# Regulators.net
KiCad netlist of a schematic drawn in Altium Designer
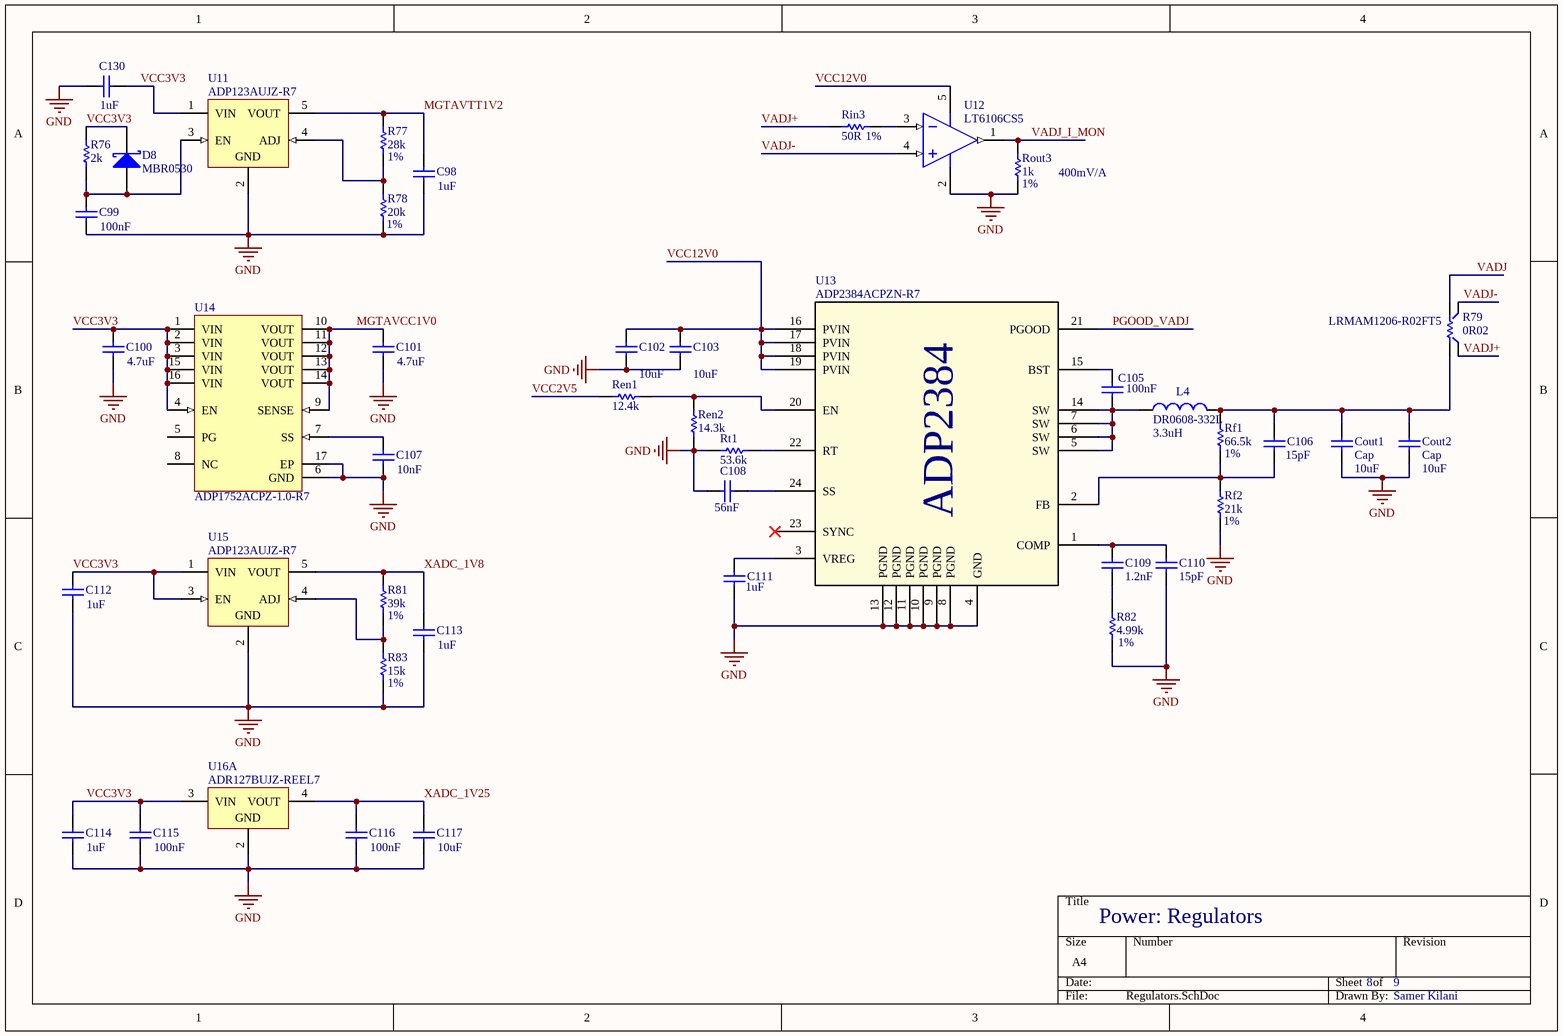
[diagram p0: Regulators.SchDoc]

(export (version "E")
  (design (tool "Eeschema 10.0.6"))
  (components
    (comp (ref "C98")
      (value "1uF")
      (footprint "C0603")
      (description "Capacitor")
      (fields (field (name "PUBLISHER") "Altium Limited"))
      (libsource (lib "atfclib") (part "Cap"))
    )
    (comp (ref "C99")
      (value "100nF")
      (footprint "C0402")
      (description "Capacitor")
      (fields (field (name "PUBLISHER") "Altium Limited"))
      (libsource (lib "atfclib") (part "Cap"))
    )
    (comp (ref "C100")
      (value "4.7uF")
      (footprint "C0603")
      (description "Capacitor")
      (fields (field (name "PUBLISHER") "Altium Limited"))
      (libsource (lib "atfclib") (part "Cap"))
    )
    (comp (ref "C101")
      (value "4.7uF")
      (footprint "C0603")
      (description "Capacitor")
      (fields (field (name "PUBLISHER") "Altium Limited"))
      (libsource (lib "atfclib") (part "Cap"))
    )
    (comp (ref "C102")
      (value "10uF")
      (footprint "C0805")
      (description "Capacitor")
      (fields (field (name "PUBLISHER") "Altium Limited"))
      (libsource (lib "atfclib") (part "Cap"))
    )
    (comp (ref "C103")
      (value "10uF")
      (footprint "C0805")
      (description "Capacitor")
      (fields (field (name "PUBLISHER") "Altium Limited"))
      (libsource (lib "atfclib") (part "Cap"))
    )
    (comp (ref "C105")
      (value "100nF")
      (footprint "C0402")
      (description "Capacitor")
      (fields (field (name "Comment") "Cap") (field (name "PUBLISHER") "Altium Limited"))
      (libsource (lib "atfclib") (part "Cap"))
    )
    (comp (ref "C106")
      (value "15pF")
      (footprint "C0402")
      (description "Capacitor")
      (fields (field (name "PUBLISHER") "Altium Limited"))
      (libsource (lib "atfclib") (part "Cap"))
    )
    (comp (ref "C107")
      (value "10nF")
      (footprint "C0603")
      (description "Capacitor")
      (fields (field (name "PUBLISHER") "Altium Limited"))
      (libsource (lib "atfclib") (part "Cap"))
    )
    (comp (ref "C108")
      (value "56nF")
      (footprint "C0402")
      (description "Capacitor")
      (fields (field (name "PUBLISHER") "Altium Limited"))
      (libsource (lib "atfclib") (part "Cap"))
    )
    (comp (ref "C109")
      (value "1.2nF")
      (footprint "C0402")
      (description "Capacitor")
      (fields (field (name "PUBLISHER") "Altium Limited"))
      (libsource (lib "atfclib") (part "Cap"))
    )
    (comp (ref "C110")
      (value "15pF")
      (footprint "C0402")
      (description "Capacitor")
      (fields (field (name "PUBLISHER") "Altium Limited"))
      (libsource (lib "atfclib") (part "Cap"))
    )
    (comp (ref "C111")
      (value "1uF")
      (footprint "C0402")
      (description "Capacitor")
      (fields (field (name "PUBLISHER") "Altium Limited"))
      (libsource (lib "atfclib") (part "Cap"))
    )
    (comp (ref "C112")
      (value "1uF")
      (footprint "C0603")
      (description "Capacitor")
      (fields (field (name "PUBLISHER") "Altium Limited"))
      (libsource (lib "atfclib") (part "Cap"))
    )
    (comp (ref "C113")
      (value "1uF")
      (footprint "C0603")
      (description "Capacitor")
      (fields (field (name "PUBLISHER") "Altium Limited"))
      (libsource (lib "atfclib") (part "Cap"))
    )
    (comp (ref "C114")
      (value "1uF")
      (footprint "C0603")
      (description "Capacitor")
      (fields (field (name "PUBLISHER") "Altium Limited"))
      (libsource (lib "atfclib") (part "Cap"))
    )
    (comp (ref "C115")
      (value "100nF")
      (footprint "C0402")
      (description "Capacitor")
      (fields (field (name "PUBLISHER") "Altium Limited"))
      (libsource (lib "atfclib") (part "Cap"))
    )
    (comp (ref "C116")
      (value "100nF")
      (footprint "C0402")
      (description "Capacitor")
      (fields (field (name "PUBLISHER") "Altium Limited"))
      (libsource (lib "atfclib") (part "Cap"))
    )
    (comp (ref "C117")
      (value "10uF")
      (footprint "C0603")
      (description "Capacitor")
      (fields (field (name "PUBLISHER") "Altium Limited"))
      (libsource (lib "atfclib") (part "Cap"))
    )
    (comp (ref "C130")
      (value "1uF")
      (footprint "C0603")
      (description "Capacitor")
      (fields (field (name "PUBLISHER") "Altium Limited"))
      (libsource (lib "atfclib") (part "Cap"))
    )
    (comp (ref "Cout1")
      (value "Cap")
      (footprint "C0805")
      (description "Capacitor")
      (fields (field (name "ALTIUM_VALUE") "10uF") (field (name "PUBLISHER") "Altium Limited"))
      (libsource (lib "atfclib") (part "Cap"))
    )
    (comp (ref "Cout2")
      (value "Cap")
      (footprint "C0805")
      (description "Capacitor")
      (fields (field (name "ALTIUM_VALUE") "10uF") (field (name "PUBLISHER") "Altium Limited"))
      (libsource (lib "atfclib") (part "Cap"))
    )
    (comp (ref "D8") (value "MBR0530") (footprint "SOD-123") (libsource (lib "atfclib") (part "MBR0530")))
    (comp (ref "L4")
      (value "DR0608-332L")
      (footprint "DR0608")
      (description "Inductor")
      (fields (field (name "ALTIUM_VALUE") "3.3uH") (field (name "PUBLISHER") "Altium Limited"))
      (libsource (lib "atfclib") (part "Inductor"))
    )
    (comp (ref "R76")
      (value "2k")
      (footprint "R0402")
      (description "Resistor")
      (fields (field (name "Comment") "Res"))
      (libsource (lib "atfclib") (part "Res"))
    )
    (comp (ref "R77")
      (value "28k")
      (footprint "R0402")
      (description "Resistor")
      (fields (field (name "TOLERANCE") "1%") (field (name "Comment") "Res"))
      (libsource (lib "atfclib") (part "Res"))
    )
    (comp (ref "R78")
      (value "20k")
      (footprint "R0402")
      (description "Resistor")
      (fields (field (name "TOLERANCE") "1%") (field (name "Comment") "Res"))
      (libsource (lib "atfclib") (part "Res"))
    )
    (comp (ref "R79")
      (value "LRMAM1206-R02FT5")
      (footprint "LRMA1206")
      (description "Resistor")
      (fields (field (name "ALTIUM_VALUE") "0R02"))
      (libsource (lib "atfclib") (part "Res_sense"))
    )
    (comp (ref "R81")
      (value "39k")
      (footprint "R0603")
      (description "Resistor")
      (fields (field (name "TOLERANCE") "1%") (field (name "Comment") "Res"))
      (libsource (lib "atfclib") (part "Res"))
    )
    (comp (ref "R82")
      (value "4.99k")
      (footprint "R0402")
      (description "Resistor")
      (fields (field (name "TOLERANCE") "1%") (field (name "Comment") "Res"))
      (libsource (lib "atfclib") (part "Res"))
    )
    (comp (ref "R83")
      (value "15k")
      (footprint "R0603")
      (description "Resistor")
      (fields (field (name "TOLERANCE") "1%") (field (name "Comment") "Res"))
      (libsource (lib "atfclib") (part "Res"))
    )
    (comp (ref "Ren1")
      (value "12.4k")
      (footprint "R0402")
      (description "Resistor")
      (fields (field (name "Comment") "Res"))
      (libsource (lib "atfclib") (part "Res"))
    )
    (comp (ref "Ren2")
      (value "14.3k")
      (footprint "R0402")
      (description "Resistor")
      (fields (field (name "Comment") "Res"))
      (libsource (lib "atfclib") (part "Res"))
    )
    (comp (ref "Rf1")
      (value "66.5k")
      (footprint "R0402")
      (description "Resistor")
      (fields (field (name "TOLERANCE") "1%") (field (name "Comment") "Res"))
      (libsource (lib "atfclib") (part "Res"))
    )
    (comp (ref "Rf2")
      (value "21k")
      (footprint "R0402")
      (description "Resistor")
      (fields (field (name "TOLERANCE") "1%") (field (name "Comment") "Res"))
      (libsource (lib "atfclib") (part "Res"))
    )
    (comp (ref "Rin3")
      (value "50R")
      (footprint "R0402")
      (description "Resistor")
      (fields (field (name "TOLERANCE") "1%") (field (name "Comment") "Res"))
      (libsource (lib "atfclib") (part "Res"))
    )
    (comp (ref "Rout3")
      (value "1k")
      (footprint "R0402")
      (description "Resistor")
      (fields (field (name "TOLERANCE") "1%") (field (name "Comment") "Res"))
      (libsource (lib "atfclib") (part "Res"))
    )
    (comp (ref "Rt1")
      (value "53.6k")
      (footprint "R0402")
      (description "Resistor")
      (fields (field (name "Comment") "Res"))
      (libsource (lib "atfclib") (part "Res"))
    )
    (comp (ref "U11")
      (value "ADP123AUJZ-R7")
      (footprint "ADI-UJ-5_N")
      (fields (field (name "MANUFACTURER") "Analog Devices"))
      (libsource (lib "atfclib") (part "ADP123AUJZ-R7"))
    )
    (comp (ref "U12")
      (value "LT6106CS5")
      (footprint "LT-S5-5-TSOT-23_N")
      (fields
        (field (name "LINEAR TECHNOLOGY PART NUMBER") "LT6106")
        (field (name "MANUFACTURER") "Linear Technology")
      )
      (libsource (lib "atfclib") (part "LT6106CS5"))
    )
    (comp (ref "U13")
      (value "ADP2384ACPZN-R7")
      (footprint "CP_24_12")
      (description "Imported")
      (libsource (lib "atfclib") (part "ADP2384ACPZN-R7"))
    )
    (comp (ref "U14")
      (value "ADP1752ACPZ-1.0-R7")
      (footprint "CP-16-4_N")
      (fields (field (name "MANUFACTURER") "Analog Devices"))
      (libsource (lib "atfclib") (part "ADP1752ACPZ-1.0-R7"))
    )
    (comp (ref "U15")
      (value "ADP123AUJZ-R7")
      (footprint "ADI-UJ-5_N")
      (fields (field (name "MANUFACTURER") "Analog Devices"))
      (libsource (lib "atfclib") (part "ADP123AUJZ-R7"))
    )
    (comp (ref "U16")
      (value "ADR127BUJZ-REEL7")
      (footprint "ADI-UJ-6_N")
      (fields (field (name "MANUFACTURER") "Analog Devices"))
      (libsource (lib "atfclib") (part "ADR127BUJZ-REEL7"))
    )
  )
  (nets
    (net (code "1") (name "/MGTAVCC1V0") (class "Default")
      (node (ref "C101") (pin "1") (pinfunction "1_1") (pintype "passive"))
      (node (ref "U14") (pin "10") (pinfunction "VOUT_10") (pintype "power_in"))
      (node (ref "U14") (pin "11") (pinfunction "VOUT_11") (pintype "power_in"))
      (node (ref "U14") (pin "12") (pinfunction "VOUT_12") (pintype "power_in"))
      (node (ref "U14") (pin "13") (pinfunction "VOUT_13") (pintype "power_in"))
      (node (ref "U14") (pin "14") (pinfunction "VOUT_14") (pintype "power_in"))
      (node (ref "U14") (pin "9") (pinfunction "SENSE_9") (pintype "input"))
    )
    (net (code "2") (name "/MGTAVTT1V2") (class "Default")
      (node (ref "C98") (pin "1") (pinfunction "1_1") (pintype "passive"))
      (node (ref "R77") (pin "2") (pinfunction "2_2") (pintype "passive"))
      (node (ref "U11") (pin "5") (pinfunction "VOUT_5") (pintype "power_in"))
    )
    (net (code "3") (name "/PGOOD_VADJ") (class "Default")
      (node (ref "U13") (pin "21") (pinfunction "PGOOD_21") (pintype "passive"))
    )
    (net (code "4") (name "/VADJ") (class "Default")
      (node (ref "R79") (pin "2") (pinfunction "2_2") (pintype "passive"))
    )
    (net (code "5") (name "/VADJ+") (class "Default")
      (node (ref "R79") (pin "3") (pinfunction "3_3") (pintype "passive"))
      (node (ref "Rin3") (pin "1") (pinfunction "1_1") (pintype "passive"))
    )
    (net (code "6") (name "/VADJ-") (class "Default")
      (node (ref "R79") (pin "4") (pinfunction "4_4") (pintype "passive"))
      (node (ref "U12") (pin "4") (pinfunction "+IN_4") (pintype "input"))
    )
    (net (code "7") (name "/VADJ_I_MON") (class "Default")
      (node (ref "Rout3") (pin "2") (pinfunction "2_2") (pintype "passive"))
      (node (ref "U12") (pin "1") (pinfunction "OUT_1") (pintype "output"))
    )
    (net (code "8") (name "/VCC2V5") (class "Default")
      (node (ref "Ren1") (pin "1") (pinfunction "1_1") (pintype "passive"))
    )
    (net (code "9") (name "/VCC3V3") (class "Default")
      (node (ref "C100") (pin "1") (pinfunction "1_1") (pintype "passive"))
      (node (ref "C112") (pin "1") (pinfunction "1_1") (pintype "passive"))
      (node (ref "C114") (pin "1") (pinfunction "1_1") (pintype "passive"))
      (node (ref "C115") (pin "1") (pinfunction "1_1") (pintype "passive"))
      (node (ref "C130") (pin "2") (pinfunction "2_2") (pintype "passive"))
      (node (ref "D8") (pin "1") (pinfunction "K_1") (pintype "passive"))
      (node (ref "R76") (pin "2") (pinfunction "2_2") (pintype "passive"))
      (node (ref "U11") (pin "1") (pinfunction "VIN_1") (pintype "power_in"))
      (node (ref "U14") (pin "1") (pinfunction "VIN_1") (pintype "power_in"))
      (node (ref "U14") (pin "15") (pinfunction "VIN_15") (pintype "power_in"))
      (node (ref "U14") (pin "16") (pinfunction "VIN_16") (pintype "power_in"))
      (node (ref "U14") (pin "2") (pinfunction "VIN_2") (pintype "power_in"))
      (node (ref "U14") (pin "3") (pinfunction "VIN_3") (pintype "power_in"))
      (node (ref "U14") (pin "4") (pinfunction "EN_4") (pintype "input"))
      (node (ref "U15") (pin "1") (pinfunction "VIN_1") (pintype "power_in"))
      (node (ref "U15") (pin "3") (pinfunction "EN_3") (pintype "input"))
      (node (ref "U16") (pin "3") (pinfunction "VIN_3") (pintype "power_in"))
    )
    (net (code "10") (name "/VCC12V0") (class "Default")
      (node (ref "C102") (pin "1") (pinfunction "1_1") (pintype "passive"))
      (node (ref "C103") (pin "1") (pinfunction "1_1") (pintype "passive"))
      (node (ref "U12") (pin "5") (pinfunction "V+_5") (pintype "power_in"))
      (node (ref "U13") (pin "16") (pinfunction "PVIN_16") (pintype "passive"))
      (node (ref "U13") (pin "17") (pinfunction "PVIN_17") (pintype "passive"))
      (node (ref "U13") (pin "18") (pinfunction "PVIN_18") (pintype "passive"))
      (node (ref "U13") (pin "19") (pinfunction "PVIN_19") (pintype "passive"))
    )
    (net (code "11") (name "/XADC_1V8") (class "Default")
      (node (ref "C113") (pin "1") (pinfunction "1_1") (pintype "passive"))
      (node (ref "R81") (pin "2") (pinfunction "2_2") (pintype "passive"))
      (node (ref "U15") (pin "5") (pinfunction "VOUT_5") (pintype "power_in"))
    )
    (net (code "12") (name "/XADC_1V25") (class "Default")
      (node (ref "C116") (pin "1") (pinfunction "1_1") (pintype "passive"))
      (node (ref "C117") (pin "1") (pinfunction "1_1") (pintype "passive"))
      (node (ref "U16") (pin "4") (pinfunction "VOUT_4") (pintype "power_in"))
    )
    (net (code "13") (name "GND") (class "Default")
      (node (ref "C100") (pin "2") (pinfunction "2_2") (pintype "passive"))
      (node (ref "C101") (pin "2") (pinfunction "2_2") (pintype "passive"))
      (node (ref "C102") (pin "2") (pinfunction "2_2") (pintype "passive"))
      (node (ref "C103") (pin "2") (pinfunction "2_2") (pintype "passive"))
      (node (ref "C107") (pin "2") (pinfunction "2_2") (pintype "passive"))
      (node (ref "C108") (pin "2") (pinfunction "2_2") (pintype "passive"))
      (node (ref "C110") (pin "2") (pinfunction "2_2") (pintype "passive"))
      (node (ref "C111") (pin "1") (pinfunction "1_1") (pintype "passive"))
      (node (ref "C112") (pin "2") (pinfunction "2_2") (pintype "passive"))
      (node (ref "C113") (pin "2") (pinfunction "2_2") (pintype "passive"))
      (node (ref "C114") (pin "2") (pinfunction "2_2") (pintype "passive"))
      (node (ref "C115") (pin "2") (pinfunction "2_2") (pintype "passive"))
      (node (ref "C116") (pin "2") (pinfunction "2_2") (pintype "passive"))
      (node (ref "C117") (pin "2") (pinfunction "2_2") (pintype "passive"))
      (node (ref "C130") (pin "1") (pinfunction "1_1") (pintype "passive"))
      (node (ref "C98") (pin "2") (pinfunction "2_2") (pintype "passive"))
      (node (ref "C99") (pin "2") (pinfunction "2_2") (pintype "passive"))
      (node (ref "Cout1") (pin "1") (pinfunction "1_1") (pintype "passive"))
      (node (ref "Cout2") (pin "1") (pinfunction "1_1") (pintype "passive"))
      (node (ref "R78") (pin "1") (pinfunction "1_1") (pintype "passive"))
      (node (ref "R82") (pin "1") (pinfunction "1_1") (pintype "passive"))
      (node (ref "R83") (pin "1") (pinfunction "1_1") (pintype "passive"))
      (node (ref "Ren2") (pin "1") (pinfunction "1_1") (pintype "passive"))
      (node (ref "Rf2") (pin "1") (pinfunction "1_1") (pintype "passive"))
      (node (ref "Rout3") (pin "1") (pinfunction "1_1") (pintype "passive"))
      (node (ref "Rt1") (pin "1") (pinfunction "1_1") (pintype "passive"))
      (node (ref "U11") (pin "2") (pinfunction "GND_2") (pintype "power_in"))
      (node (ref "U12") (pin "2") (pinfunction "V-_2") (pintype "power_in"))
      (node (ref "U13") (pin "10") (pinfunction "PGND_10") (pintype "passive"))
      (node (ref "U13") (pin "11") (pinfunction "PGND_11") (pintype "passive"))
      (node (ref "U13") (pin "12") (pinfunction "PGND_12") (pintype "passive"))
      (node (ref "U13") (pin "13") (pinfunction "PGND_13") (pintype "passive"))
      (node (ref "U13") (pin "4") (pinfunction "GND_4") (pintype "passive"))
      (node (ref "U13") (pin "8") (pinfunction "PGND_8") (pintype "passive"))
      (node (ref "U13") (pin "9") (pinfunction "PGND_9") (pintype "passive"))
      (node (ref "U14") (pin "17") (pinfunction "EP_17") (pintype "power_in"))
      (node (ref "U14") (pin "6") (pinfunction "GND_6") (pintype "power_in"))
      (node (ref "U15") (pin "2") (pinfunction "GND_2") (pintype "power_in"))
      (node (ref "U16") (pin "2") (pinfunction "GND_2") (pintype "power_in"))
    )
    (net (code "14") (name "Net-(C105-Pad1)") (class "Default")
      (node (ref "C105") (pin "1") (pinfunction "1_1") (pintype "passive"))
      (node (ref "L4") (pin "1") (pinfunction "1_1") (pintype "passive"))
      (node (ref "U13") (pin "14") (pinfunction "SW_14") (pintype "passive"))
      (node (ref "U13") (pin "5") (pinfunction "SW_5") (pintype "passive"))
      (node (ref "U13") (pin "6") (pinfunction "SW_6") (pintype "passive"))
      (node (ref "U13") (pin "7") (pinfunction "SW_7") (pintype "passive"))
    )
    (net (code "15") (name "Net-(C106-Pad1)") (class "Default")
      (node (ref "C106") (pin "1") (pinfunction "1_1") (pintype "passive"))
      (node (ref "Cout1") (pin "2") (pinfunction "2_2") (pintype "passive"))
      (node (ref "Cout2") (pin "2") (pinfunction "2_2") (pintype "passive"))
      (node (ref "L4") (pin "2") (pinfunction "2_2") (pintype "passive"))
      (node (ref "R79") (pin "1") (pinfunction "1_1") (pintype "passive"))
      (node (ref "Rf1") (pin "2") (pinfunction "2_2") (pintype "passive"))
    )
    (net (code "16") (name "Net-(C109-Pad2)") (class "Default")
      (node (ref "C109") (pin "2") (pinfunction "2_2") (pintype "passive"))
      (node (ref "R82") (pin "2") (pinfunction "2_2") (pintype "passive"))
    )
    (net (code "17") (name "Net-(D8-A)") (class "Default")
      (node (ref "C99") (pin "1") (pinfunction "1_1") (pintype "passive"))
      (node (ref "D8") (pin "2") (pinfunction "A_2") (pintype "passive"))
      (node (ref "R76") (pin "1") (pinfunction "1_1") (pintype "passive"))
      (node (ref "U11") (pin "3") (pinfunction "EN_3") (pintype "input"))
    )
    (net (code "18") (name "Net-(U11-ADJ)") (class "Default")
      (node (ref "R77") (pin "1") (pinfunction "1_1") (pintype "passive"))
      (node (ref "R78") (pin "2") (pinfunction "2_2") (pintype "passive"))
      (node (ref "U11") (pin "4") (pinfunction "ADJ_4") (pintype "input"))
    )
    (net (code "19") (name "Net-(U12--IN)") (class "Default")
      (node (ref "Rin3") (pin "2") (pinfunction "2_2") (pintype "passive"))
      (node (ref "U12") (pin "3") (pinfunction "-IN_3") (pintype "input"))
    )
    (net (code "20") (name "Net-(U13-BST)") (class "Default")
      (node (ref "C105") (pin "2") (pinfunction "2_2") (pintype "passive"))
      (node (ref "U13") (pin "15") (pinfunction "BST_15") (pintype "passive"))
    )
    (net (code "21") (name "Net-(U13-COMP)") (class "Default")
      (node (ref "C109") (pin "1") (pinfunction "1_1") (pintype "passive"))
      (node (ref "C110") (pin "1") (pinfunction "1_1") (pintype "passive"))
      (node (ref "U13") (pin "1") (pinfunction "COMP_1") (pintype "passive"))
    )
    (net (code "22") (name "Net-(U13-EN)") (class "Default")
      (node (ref "Ren1") (pin "2") (pinfunction "2_2") (pintype "passive"))
      (node (ref "Ren2") (pin "2") (pinfunction "2_2") (pintype "passive"))
      (node (ref "U13") (pin "20") (pinfunction "EN_20") (pintype "passive"))
    )
    (net (code "23") (name "Net-(U13-FB)") (class "Default")
      (node (ref "C106") (pin "2") (pinfunction "2_2") (pintype "passive"))
      (node (ref "Rf1") (pin "1") (pinfunction "1_1") (pintype "passive"))
      (node (ref "Rf2") (pin "2") (pinfunction "2_2") (pintype "passive"))
      (node (ref "U13") (pin "2") (pinfunction "FB_2") (pintype "passive"))
    )
    (net (code "24") (name "Net-(U13-RT)") (class "Default")
      (node (ref "Rt1") (pin "2") (pinfunction "2_2") (pintype "passive"))
      (node (ref "U13") (pin "22") (pinfunction "RT_22") (pintype "passive"))
    )
    (net (code "25") (name "Net-(U13-SS)") (class "Default")
      (node (ref "C108") (pin "1") (pinfunction "1_1") (pintype "passive"))
      (node (ref "U13") (pin "24") (pinfunction "SS_24") (pintype "passive"))
    )
    (net (code "26") (name "Net-(U13-VREG)") (class "Default")
      (node (ref "C111") (pin "2") (pinfunction "2_2") (pintype "passive"))
      (node (ref "U13") (pin "3") (pinfunction "VREG_3") (pintype "passive"))
    )
    (net (code "27") (name "Net-(U14-SS)") (class "Default")
      (node (ref "C107") (pin "1") (pinfunction "1_1") (pintype "passive"))
      (node (ref "U14") (pin "7") (pinfunction "SS_7") (pintype "input"))
    )
    (net (code "28") (name "Net-(U15-ADJ)") (class "Default")
      (node (ref "R81") (pin "1") (pinfunction "1_1") (pintype "passive"))
      (node (ref "R83") (pin "2") (pinfunction "2_2") (pintype "passive"))
      (node (ref "U15") (pin "4") (pinfunction "ADJ_4") (pintype "input"))
    )
    (net (code "29") (name "unconnected-(U13-SYNC-Pad23)") (class "Default")
      (node (ref "U13") (pin "23") (pinfunction "SYNC_23") (pintype "passive+no_connect"))
    )
    (net (code "30") (name "unconnected-(U14-NC-Pad8)") (class "Default")
      (node (ref "U14") (pin "8") (pinfunction "NC_8") (pintype "passive"))
    )
    (net (code "31") (name "unconnected-(U14-PG-Pad5)") (class "Default")
      (node (ref "U14") (pin "5") (pinfunction "PG_5") (pintype "open_collector"))
    )
  )
)
